# v0_1.net
KiCad netlist of a schematic drawn in EAGLE
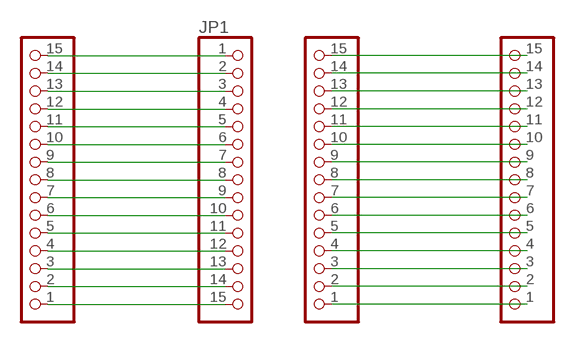
[diagram p0: schematic, sheet 1]

(export (version "E")
  (design (tool "Eeschema 10.0.6"))
  (components
    (comp (ref "JP1")
      (value "PINHD-1X15-CASTELLATED")
      (footprint "eagle-import:1X15-CASTELL")
      (libsource (lib "eagle-import") (part "PINHD-1X15-CASTELLATED"))
    )
    (comp (ref "JP2")
      (value "PINHD-1X15-CASTELLATED")
      (footprint "eagle-import:1X15-CASTELL")
      (libsource (lib "eagle-import") (part "PINHD-1X15-CASTELLATED"))
    )
    (comp (ref "JP3")
      (value "PINHD-1X15-CASTELLATED")
      (footprint "eagle-import:1X15-CASTELL")
      (libsource (lib "eagle-import") (part "PINHD-1X15-CASTELLATED"))
    )
    (comp (ref "JP4")
      (value "PINHD-1X15-CASTELLATED")
      (footprint "eagle-import:1X15-CASTELL")
      (libsource (lib "eagle-import") (part "PINHD-1X15-CASTELLATED"))
    )
  )
  (nets
    (net (code "1") (name "Net-(JP1-Pad1)") (class "Default")
      (node (ref "JP1") (pin "1") (pinfunction "1_1") (pintype "passive"))
      (node (ref "JP2") (pin "15") (pinfunction "15_15") (pintype "passive"))
    )
    (net (code "2") (name "Net-(JP1-Pad2)") (class "Default")
      (node (ref "JP1") (pin "2") (pinfunction "2_2") (pintype "passive"))
      (node (ref "JP2") (pin "14") (pinfunction "14_14") (pintype "passive"))
    )
    (net (code "3") (name "Net-(JP1-Pad3)") (class "Default")
      (node (ref "JP1") (pin "3") (pinfunction "3_3") (pintype "passive"))
      (node (ref "JP2") (pin "13") (pinfunction "13_13") (pintype "passive"))
    )
    (net (code "4") (name "Net-(JP1-Pad4)") (class "Default")
      (node (ref "JP1") (pin "4") (pinfunction "4_4") (pintype "passive"))
      (node (ref "JP2") (pin "12") (pinfunction "12_12") (pintype "passive"))
    )
    (net (code "5") (name "Net-(JP1-Pad5)") (class "Default")
      (node (ref "JP1") (pin "5") (pinfunction "5_5") (pintype "passive"))
      (node (ref "JP2") (pin "11") (pinfunction "11_11") (pintype "passive"))
    )
    (net (code "6") (name "Net-(JP1-Pad6)") (class "Default")
      (node (ref "JP1") (pin "6") (pinfunction "6_6") (pintype "passive"))
      (node (ref "JP2") (pin "10") (pinfunction "10_10") (pintype "passive"))
    )
    (net (code "7") (name "Net-(JP1-Pad7)") (class "Default")
      (node (ref "JP1") (pin "7") (pinfunction "7_7") (pintype "passive"))
      (node (ref "JP2") (pin "9") (pinfunction "9_9") (pintype "passive"))
    )
    (net (code "8") (name "Net-(JP1-Pad8)") (class "Default")
      (node (ref "JP1") (pin "8") (pinfunction "8_8") (pintype "passive"))
      (node (ref "JP2") (pin "8") (pinfunction "8_8") (pintype "passive"))
    )
    (net (code "9") (name "Net-(JP1-Pad9)") (class "Default")
      (node (ref "JP1") (pin "9") (pinfunction "9_9") (pintype "passive"))
      (node (ref "JP2") (pin "7") (pinfunction "7_7") (pintype "passive"))
    )
    (net (code "10") (name "Net-(JP1-Pad10)") (class "Default")
      (node (ref "JP1") (pin "10") (pinfunction "10_10") (pintype "passive"))
      (node (ref "JP2") (pin "6") (pinfunction "6_6") (pintype "passive"))
    )
    (net (code "11") (name "Net-(JP1-Pad11)") (class "Default")
      (node (ref "JP1") (pin "11") (pinfunction "11_11") (pintype "passive"))
      (node (ref "JP2") (pin "5") (pinfunction "5_5") (pintype "passive"))
    )
    (net (code "12") (name "Net-(JP1-Pad12)") (class "Default")
      (node (ref "JP1") (pin "12") (pinfunction "12_12") (pintype "passive"))
      (node (ref "JP2") (pin "4") (pinfunction "4_4") (pintype "passive"))
    )
    (net (code "13") (name "Net-(JP1-Pad13)") (class "Default")
      (node (ref "JP1") (pin "13") (pinfunction "13_13") (pintype "passive"))
      (node (ref "JP2") (pin "3") (pinfunction "3_3") (pintype "passive"))
    )
    (net (code "14") (name "Net-(JP1-Pad14)") (class "Default")
      (node (ref "JP1") (pin "14") (pinfunction "14_14") (pintype "passive"))
      (node (ref "JP2") (pin "2") (pinfunction "2_2") (pintype "passive"))
    )
    (net (code "15") (name "Net-(JP1-Pad15)") (class "Default")
      (node (ref "JP1") (pin "15") (pinfunction "15_15") (pintype "passive"))
      (node (ref "JP2") (pin "1") (pinfunction "1_1") (pintype "passive"))
    )
    (net (code "16") (name "Net-(JP3-Pad1)") (class "Default")
      (node (ref "JP3") (pin "1") (pinfunction "1_1") (pintype "passive"))
      (node (ref "JP4") (pin "1") (pinfunction "1_1") (pintype "passive"))
    )
    (net (code "17") (name "Net-(JP3-Pad2)") (class "Default")
      (node (ref "JP3") (pin "2") (pinfunction "2_2") (pintype "passive"))
      (node (ref "JP4") (pin "2") (pinfunction "2_2") (pintype "passive"))
    )
    (net (code "18") (name "Net-(JP3-Pad3)") (class "Default")
      (node (ref "JP3") (pin "3") (pinfunction "3_3") (pintype "passive"))
      (node (ref "JP4") (pin "3") (pinfunction "3_3") (pintype "passive"))
    )
    (net (code "19") (name "Net-(JP3-Pad4)") (class "Default")
      (node (ref "JP3") (pin "4") (pinfunction "4_4") (pintype "passive"))
      (node (ref "JP4") (pin "4") (pinfunction "4_4") (pintype "passive"))
    )
    (net (code "20") (name "Net-(JP3-Pad5)") (class "Default")
      (node (ref "JP3") (pin "5") (pinfunction "5_5") (pintype "passive"))
      (node (ref "JP4") (pin "5") (pinfunction "5_5") (pintype "passive"))
    )
    (net (code "21") (name "Net-(JP3-Pad6)") (class "Default")
      (node (ref "JP3") (pin "6") (pinfunction "6_6") (pintype "passive"))
      (node (ref "JP4") (pin "6") (pinfunction "6_6") (pintype "passive"))
    )
    (net (code "22") (name "Net-(JP3-Pad7)") (class "Default")
      (node (ref "JP3") (pin "7") (pinfunction "7_7") (pintype "passive"))
      (node (ref "JP4") (pin "7") (pinfunction "7_7") (pintype "passive"))
    )
    (net (code "23") (name "Net-(JP3-Pad8)") (class "Default")
      (node (ref "JP3") (pin "8") (pinfunction "8_8") (pintype "passive"))
      (node (ref "JP4") (pin "8") (pinfunction "8_8") (pintype "passive"))
    )
    (net (code "24") (name "Net-(JP3-Pad9)") (class "Default")
      (node (ref "JP3") (pin "9") (pinfunction "9_9") (pintype "passive"))
      (node (ref "JP4") (pin "9") (pinfunction "9_9") (pintype "passive"))
    )
    (net (code "25") (name "Net-(JP3-Pad10)") (class "Default")
      (node (ref "JP3") (pin "10") (pinfunction "10_10") (pintype "passive"))
      (node (ref "JP4") (pin "10") (pinfunction "10_10") (pintype "passive"))
    )
    (net (code "26") (name "Net-(JP3-Pad11)") (class "Default")
      (node (ref "JP3") (pin "11") (pinfunction "11_11") (pintype "passive"))
      (node (ref "JP4") (pin "11") (pinfunction "11_11") (pintype "passive"))
    )
    (net (code "27") (name "Net-(JP3-Pad12)") (class "Default")
      (node (ref "JP3") (pin "12") (pinfunction "12_12") (pintype "passive"))
      (node (ref "JP4") (pin "12") (pinfunction "12_12") (pintype "passive"))
    )
    (net (code "28") (name "Net-(JP3-Pad13)") (class "Default")
      (node (ref "JP3") (pin "13") (pinfunction "13_13") (pintype "passive"))
      (node (ref "JP4") (pin "13") (pinfunction "13_13") (pintype "passive"))
    )
    (net (code "29") (name "Net-(JP3-Pad14)") (class "Default")
      (node (ref "JP3") (pin "14") (pinfunction "14_14") (pintype "passive"))
      (node (ref "JP4") (pin "14") (pinfunction "14_14") (pintype "passive"))
    )
    (net (code "30") (name "Net-(JP3-Pad15)") (class "Default")
      (node (ref "JP3") (pin "15") (pinfunction "15_15") (pintype "passive"))
      (node (ref "JP4") (pin "15") (pinfunction "15_15") (pintype "passive"))
    )
  )
)
